# top_plank.net
KiCad netlist of a schematic drawn in EAGLE
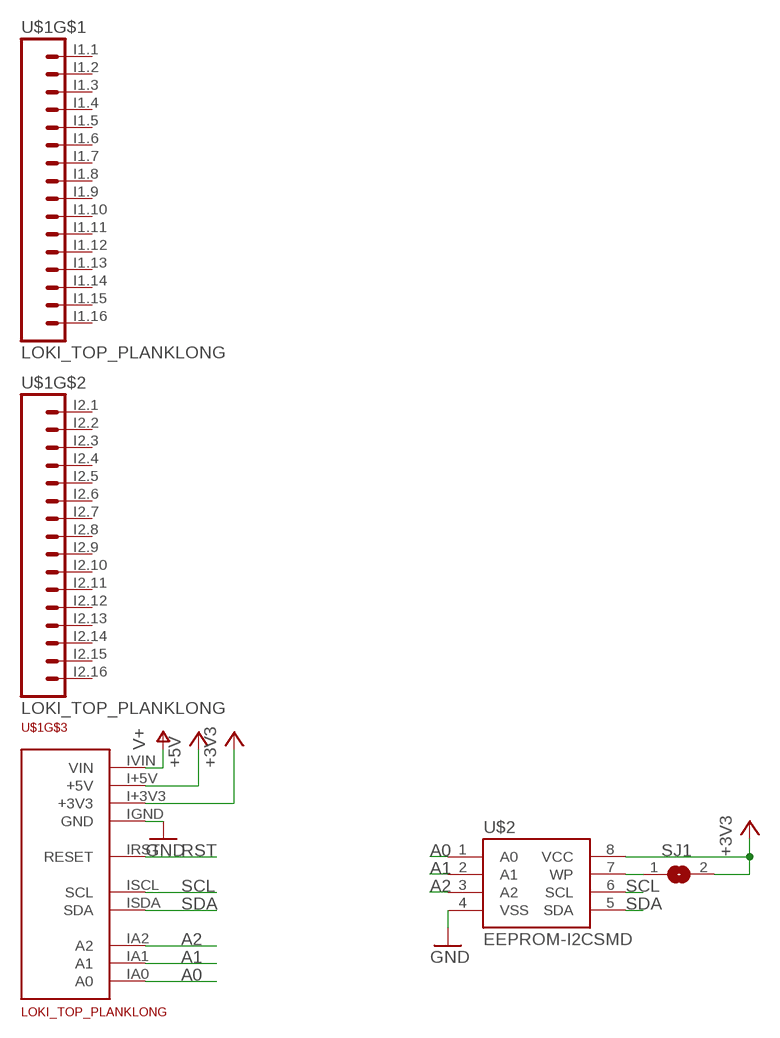
[diagram p0: schematic, sheet 1]

(export (version "E")
  (design (tool "Eeschema 10.0.6"))
  (components
    (comp (ref "SJ1") (value "SJ") (footprint "eagle-import:SJ") (libsource (lib "eagle-import") (part "SJ")))
    (comp (ref "U$1")
      (value "LOKI_TOP_PLANKLONG")
      (footprint "eagle-import:TOP_PLANK_LONG")
      (libsource (lib "eagle-import") (part "LOKI_TOP_PLANKLONG"))
    )
    (comp (ref "U$2")
      (value "EEPROM-I2CSMD")
      (footprint "eagle-import:SO08")
      (libsource (lib "eagle-import") (part "EEPROM-I2CSMD"))
    )
  )
  (nets
    (net (code "1") (name "+3V3") (class "Default")
      (node (ref "SJ1") (pin "2") (pinfunction "2_2") (pintype "passive"))
      (node (ref "U$1") (pin "I+3V3") (pinfunction "+3V3_I+3V3") (pintype "power_in"))
      (node (ref "U$2") (pin "8") (pinfunction "VCC_8") (pintype "power_in"))
    )
    (net (code "2") (name "+5V") (class "Default")
      (node (ref "U$1") (pin "I+5V") (pinfunction "+5V_I+5V") (pintype "power_in"))
    )
    (net (code "3") (name "/A0") (class "Default")
      (node (ref "U$1") (pin "IA0") (pinfunction "A0_IA0") (pintype "output"))
      (node (ref "U$2") (pin "1") (pinfunction "A0_1") (pintype "bidirectional"))
    )
    (net (code "4") (name "/A1") (class "Default")
      (node (ref "U$1") (pin "IA1") (pinfunction "A1_IA1") (pintype "output"))
      (node (ref "U$2") (pin "2") (pinfunction "A1_2") (pintype "bidirectional"))
    )
    (net (code "5") (name "/A2") (class "Default")
      (node (ref "U$1") (pin "IA2") (pinfunction "A2_IA2") (pintype "output"))
      (node (ref "U$2") (pin "3") (pinfunction "A2_3") (pintype "bidirectional"))
    )
    (net (code "6") (name "/RST") (class "Default")
      (node (ref "U$1") (pin "IRST") (pinfunction "RESET_IRST") (pintype "input"))
    )
    (net (code "7") (name "/SCL") (class "Default")
      (node (ref "U$1") (pin "ISCL") (pinfunction "SCL_ISCL") (pintype "bidirectional"))
      (node (ref "U$2") (pin "6") (pinfunction "SCL_6") (pintype "bidirectional"))
    )
    (net (code "8") (name "/SDA") (class "Default")
      (node (ref "U$1") (pin "ISDA") (pinfunction "SDA_ISDA") (pintype "bidirectional"))
      (node (ref "U$2") (pin "5") (pinfunction "SDA_5") (pintype "bidirectional"))
    )
    (net (code "9") (name "GND") (class "Default")
      (node (ref "U$1") (pin "IGND") (pinfunction "GND_IGND") (pintype "power_in"))
      (node (ref "U$2") (pin "4") (pinfunction "VSS_4") (pintype "power_in"))
    )
    (net (code "10") (name "Net-(U$2-WP)") (class "Default")
      (node (ref "SJ1") (pin "1") (pinfunction "1_1") (pintype "passive"))
      (node (ref "U$2") (pin "7") (pinfunction "WP_7") (pintype "bidirectional"))
    )
    (net (code "11") (name "V+") (class "Default")
      (node (ref "U$1") (pin "IVIN") (pinfunction "VIN_IVIN") (pintype "power_in"))
    )
    (net (code "12") (name "unconnected-(U$1A-1-PadI1.1)") (class "Default")
      (node (ref "U$1") (pin "I1.1") (pinfunction "1_I1.1") (pintype "passive"))
    )
    (net (code "13") (name "unconnected-(U$1A-2-PadI1.2)") (class "Default")
      (node (ref "U$1") (pin "I1.2") (pinfunction "2_I1.2") (pintype "passive"))
    )
    (net (code "14") (name "unconnected-(U$1A-3-PadI1.3)") (class "Default")
      (node (ref "U$1") (pin "I1.3") (pinfunction "3_I1.3") (pintype "passive"))
    )
    (net (code "15") (name "unconnected-(U$1A-4-PadI1.4)") (class "Default")
      (node (ref "U$1") (pin "I1.4") (pinfunction "4_I1.4") (pintype "passive"))
    )
    (net (code "16") (name "unconnected-(U$1A-5-PadI1.5)") (class "Default")
      (node (ref "U$1") (pin "I1.5") (pinfunction "5_I1.5") (pintype "passive"))
    )
    (net (code "17") (name "unconnected-(U$1A-6-PadI1.6)") (class "Default")
      (node (ref "U$1") (pin "I1.6") (pinfunction "6_I1.6") (pintype "passive"))
    )
    (net (code "18") (name "unconnected-(U$1A-7-PadI1.7)") (class "Default")
      (node (ref "U$1") (pin "I1.7") (pinfunction "7_I1.7") (pintype "passive"))
    )
    (net (code "19") (name "unconnected-(U$1A-8-PadI1.8)") (class "Default")
      (node (ref "U$1") (pin "I1.8") (pinfunction "8_I1.8") (pintype "passive"))
    )
    (net (code "20") (name "unconnected-(U$1A-9-PadI1.9)") (class "Default")
      (node (ref "U$1") (pin "I1.9") (pinfunction "9_I1.9") (pintype "passive"))
    )
    (net (code "21") (name "unconnected-(U$1A-10-PadI1.10)") (class "Default")
      (node (ref "U$1") (pin "I1.10") (pinfunction "10_I1.10") (pintype "passive"))
    )
    (net (code "22") (name "unconnected-(U$1A-11-PadI1.11)") (class "Default")
      (node (ref "U$1") (pin "I1.11") (pinfunction "11_I1.11") (pintype "passive"))
    )
    (net (code "23") (name "unconnected-(U$1A-12-PadI1.12)") (class "Default")
      (node (ref "U$1") (pin "I1.12") (pinfunction "12_I1.12") (pintype "passive"))
    )
    (net (code "24") (name "unconnected-(U$1A-13-PadI1.13)") (class "Default")
      (node (ref "U$1") (pin "I1.13") (pinfunction "13_I1.13") (pintype "passive"))
    )
    (net (code "25") (name "unconnected-(U$1A-14-PadI1.14)") (class "Default")
      (node (ref "U$1") (pin "I1.14") (pinfunction "14_I1.14") (pintype "passive"))
    )
    (net (code "26") (name "unconnected-(U$1A-15-PadI1.15)") (class "Default")
      (node (ref "U$1") (pin "I1.15") (pinfunction "15_I1.15") (pintype "passive"))
    )
    (net (code "27") (name "unconnected-(U$1A-16-PadI1.16)") (class "Default")
      (node (ref "U$1") (pin "I1.16") (pinfunction "16_I1.16") (pintype "passive"))
    )
    (net (code "28") (name "unconnected-(U$1B-1-PadI2.1)") (class "Default")
      (node (ref "U$1") (pin "I2.1") (pinfunction "1_I2.1") (pintype "passive"))
    )
    (net (code "29") (name "unconnected-(U$1B-2-PadI2.2)") (class "Default")
      (node (ref "U$1") (pin "I2.2") (pinfunction "2_I2.2") (pintype "passive"))
    )
    (net (code "30") (name "unconnected-(U$1B-3-PadI2.3)") (class "Default")
      (node (ref "U$1") (pin "I2.3") (pinfunction "3_I2.3") (pintype "passive"))
    )
    (net (code "31") (name "unconnected-(U$1B-4-PadI2.4)") (class "Default")
      (node (ref "U$1") (pin "I2.4") (pinfunction "4_I2.4") (pintype "passive"))
    )
    (net (code "32") (name "unconnected-(U$1B-5-PadI2.5)") (class "Default")
      (node (ref "U$1") (pin "I2.5") (pinfunction "5_I2.5") (pintype "passive"))
    )
    (net (code "33") (name "unconnected-(U$1B-6-PadI2.6)") (class "Default")
      (node (ref "U$1") (pin "I2.6") (pinfunction "6_I2.6") (pintype "passive"))
    )
    (net (code "34") (name "unconnected-(U$1B-7-PadI2.7)") (class "Default")
      (node (ref "U$1") (pin "I2.7") (pinfunction "7_I2.7") (pintype "passive"))
    )
    (net (code "35") (name "unconnected-(U$1B-8-PadI2.8)") (class "Default")
      (node (ref "U$1") (pin "I2.8") (pinfunction "8_I2.8") (pintype "passive"))
    )
    (net (code "36") (name "unconnected-(U$1B-9-PadI2.9)") (class "Default")
      (node (ref "U$1") (pin "I2.9") (pinfunction "9_I2.9") (pintype "passive"))
    )
    (net (code "37") (name "unconnected-(U$1B-10-PadI2.10)") (class "Default")
      (node (ref "U$1") (pin "I2.10") (pinfunction "10_I2.10") (pintype "passive"))
    )
    (net (code "38") (name "unconnected-(U$1B-11-PadI2.11)") (class "Default")
      (node (ref "U$1") (pin "I2.11") (pinfunction "11_I2.11") (pintype "passive"))
    )
    (net (code "39") (name "unconnected-(U$1B-12-PadI2.12)") (class "Default")
      (node (ref "U$1") (pin "I2.12") (pinfunction "12_I2.12") (pintype "passive"))
    )
    (net (code "40") (name "unconnected-(U$1B-13-PadI2.13)") (class "Default")
      (node (ref "U$1") (pin "I2.13") (pinfunction "13_I2.13") (pintype "passive"))
    )
    (net (code "41") (name "unconnected-(U$1B-14-PadI2.14)") (class "Default")
      (node (ref "U$1") (pin "I2.14") (pinfunction "14_I2.14") (pintype "passive"))
    )
    (net (code "42") (name "unconnected-(U$1B-15-PadI2.15)") (class "Default")
      (node (ref "U$1") (pin "I2.15") (pinfunction "15_I2.15") (pintype "passive"))
    )
    (net (code "43") (name "unconnected-(U$1B-16-PadI2.16)") (class "Default")
      (node (ref "U$1") (pin "I2.16") (pinfunction "16_I2.16") (pintype "passive"))
    )
  )
)
